# mini-usb-breakout.net
KiCad netlist of a schematic drawn in EAGLE
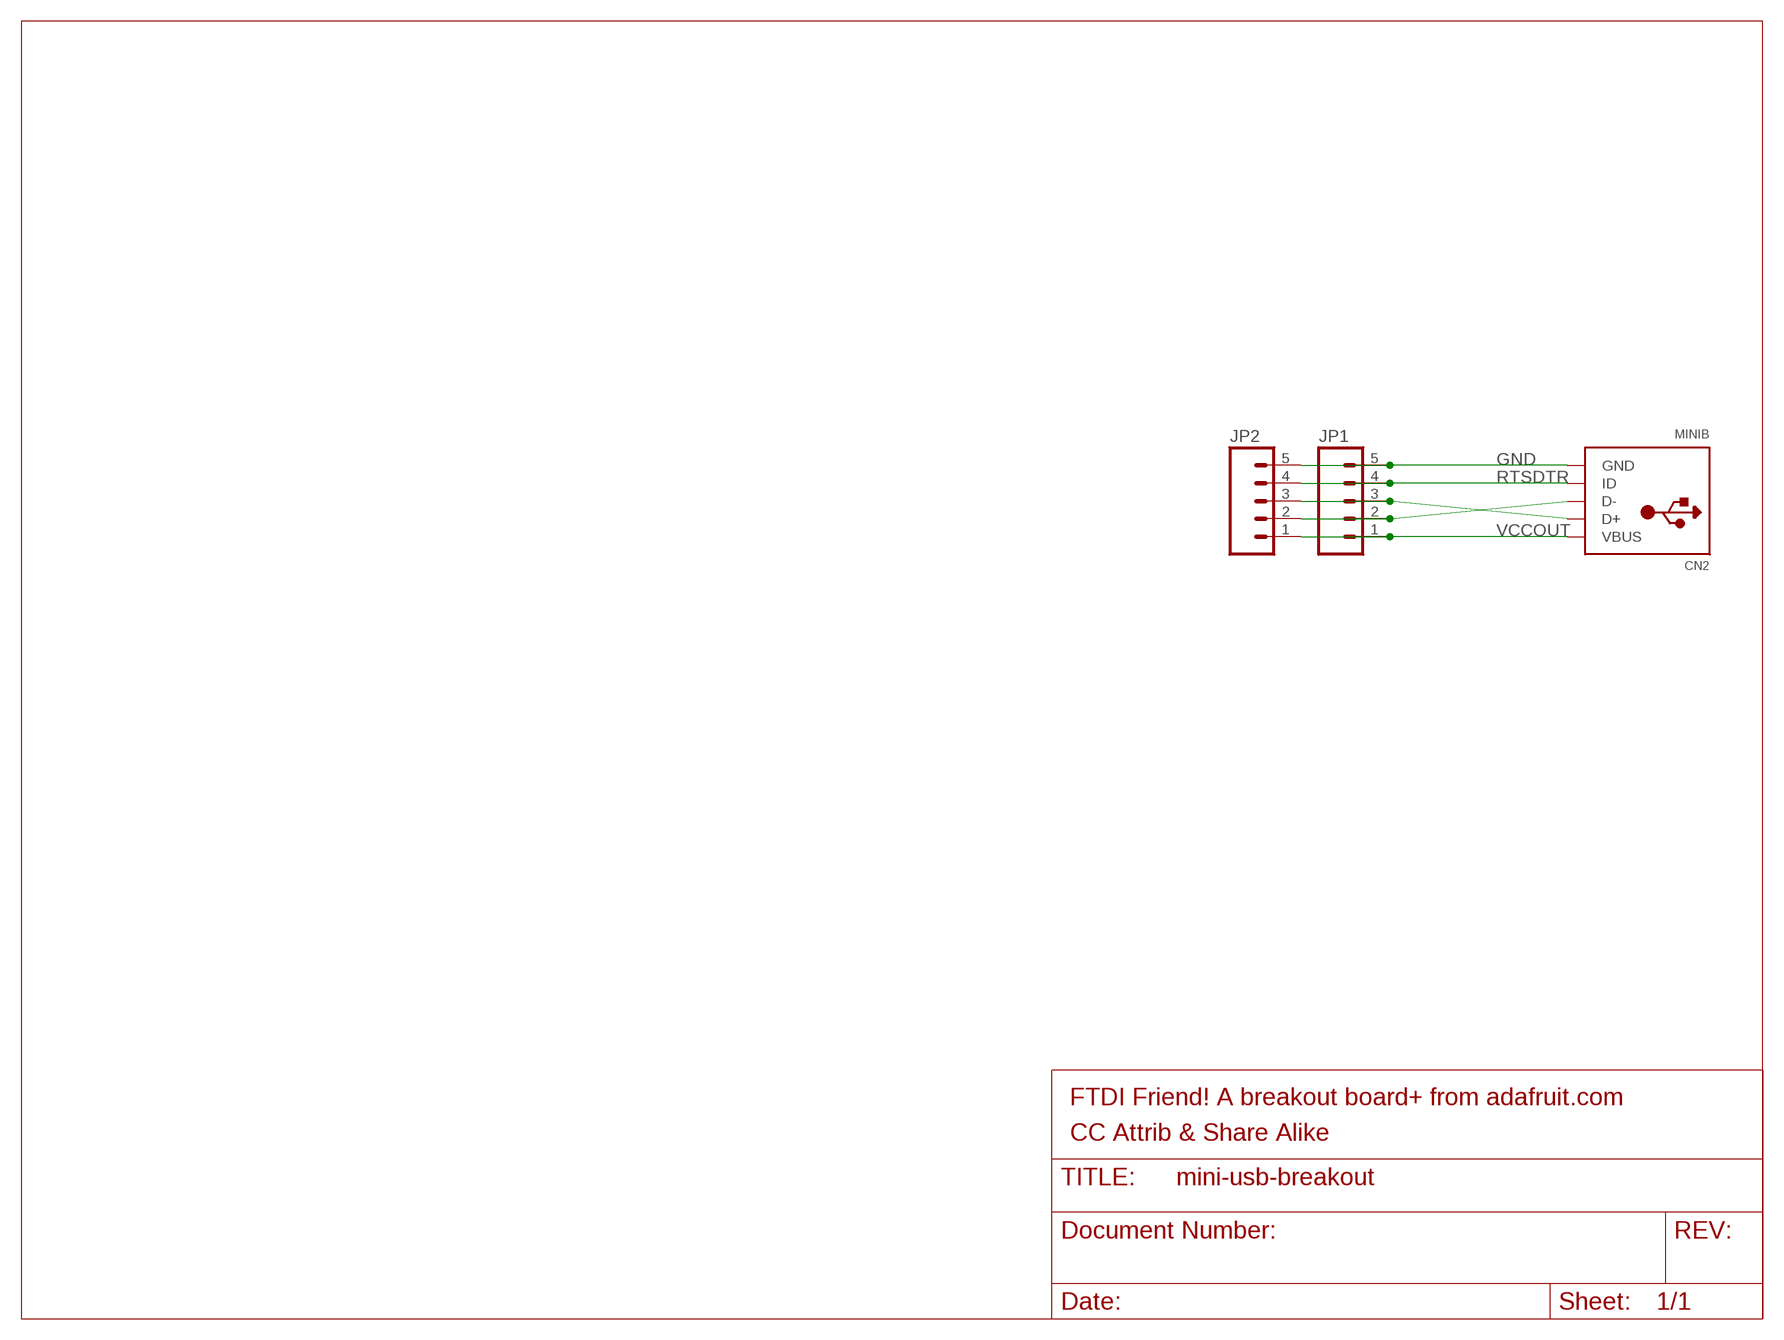
[diagram p0: schematic, sheet 1]

(export (version "E")
  (design (tool "Eeschema 10.0.6"))
  (components
    (comp (ref "CN2")
      (value "MINIB")
      (footprint "eagle-import:USB-MINIB")
      (libsource (lib "eagle-import") (part "USBMINIB"))
    )
    (comp (ref "JP1")
      (value "M05PTH")
      (footprint "eagle-import:1X05")
      (libsource (lib "eagle-import") (part "M05PTH"))
    )
    (comp (ref "JP2")
      (value "M05PTH")
      (footprint "eagle-import:1X05")
      (libsource (lib "eagle-import") (part "M05PTH"))
    )
  )
  (nets
    (net (code "1") (name "/GND") (class "Default")
      (node (ref "CN2") (pin "GND") (pinfunction "GND_GND") (pintype "power_in"))
      (node (ref "JP1") (pin "5") (pinfunction "5_5") (pintype "passive"))
      (node (ref "JP2") (pin "5") (pinfunction "5_5") (pintype "passive"))
    )
    (net (code "2") (name "/RTSDTR") (class "Default")
      (node (ref "CN2") (pin "ID") (pinfunction "ID_ID") (pintype "bidirectional"))
      (node (ref "JP1") (pin "4") (pinfunction "4_4") (pintype "passive"))
      (node (ref "JP2") (pin "4") (pinfunction "4_4") (pintype "passive"))
    )
    (net (code "3") (name "/VCCOUT") (class "Default")
      (node (ref "CN2") (pin "VBUS") (pinfunction "VBUS_VBUS") (pintype "power_in"))
      (node (ref "JP1") (pin "1") (pinfunction "1_1") (pintype "passive"))
      (node (ref "JP2") (pin "1") (pinfunction "1_1") (pintype "passive"))
    )
    (net (code "4") (name "Net-(CN2-PadD+)") (class "Default")
      (node (ref "CN2") (pin "D+") (pinfunction "D+_D+") (pintype "bidirectional"))
      (node (ref "JP1") (pin "3") (pinfunction "3_3") (pintype "passive"))
      (node (ref "JP2") (pin "3") (pinfunction "3_3") (pintype "passive"))
    )
    (net (code "5") (name "Net-(CN2-PadD-)") (class "Default")
      (node (ref "CN2") (pin "D-") (pinfunction "D-_D-") (pintype "bidirectional"))
      (node (ref "JP1") (pin "2") (pinfunction "2_2") (pintype "passive"))
      (node (ref "JP2") (pin "2") (pinfunction "2_2") (pintype "passive"))
    )
  )
)
